# SCH_task-L2.net
KiCad netlist of a schematic drawn in EasyEDA
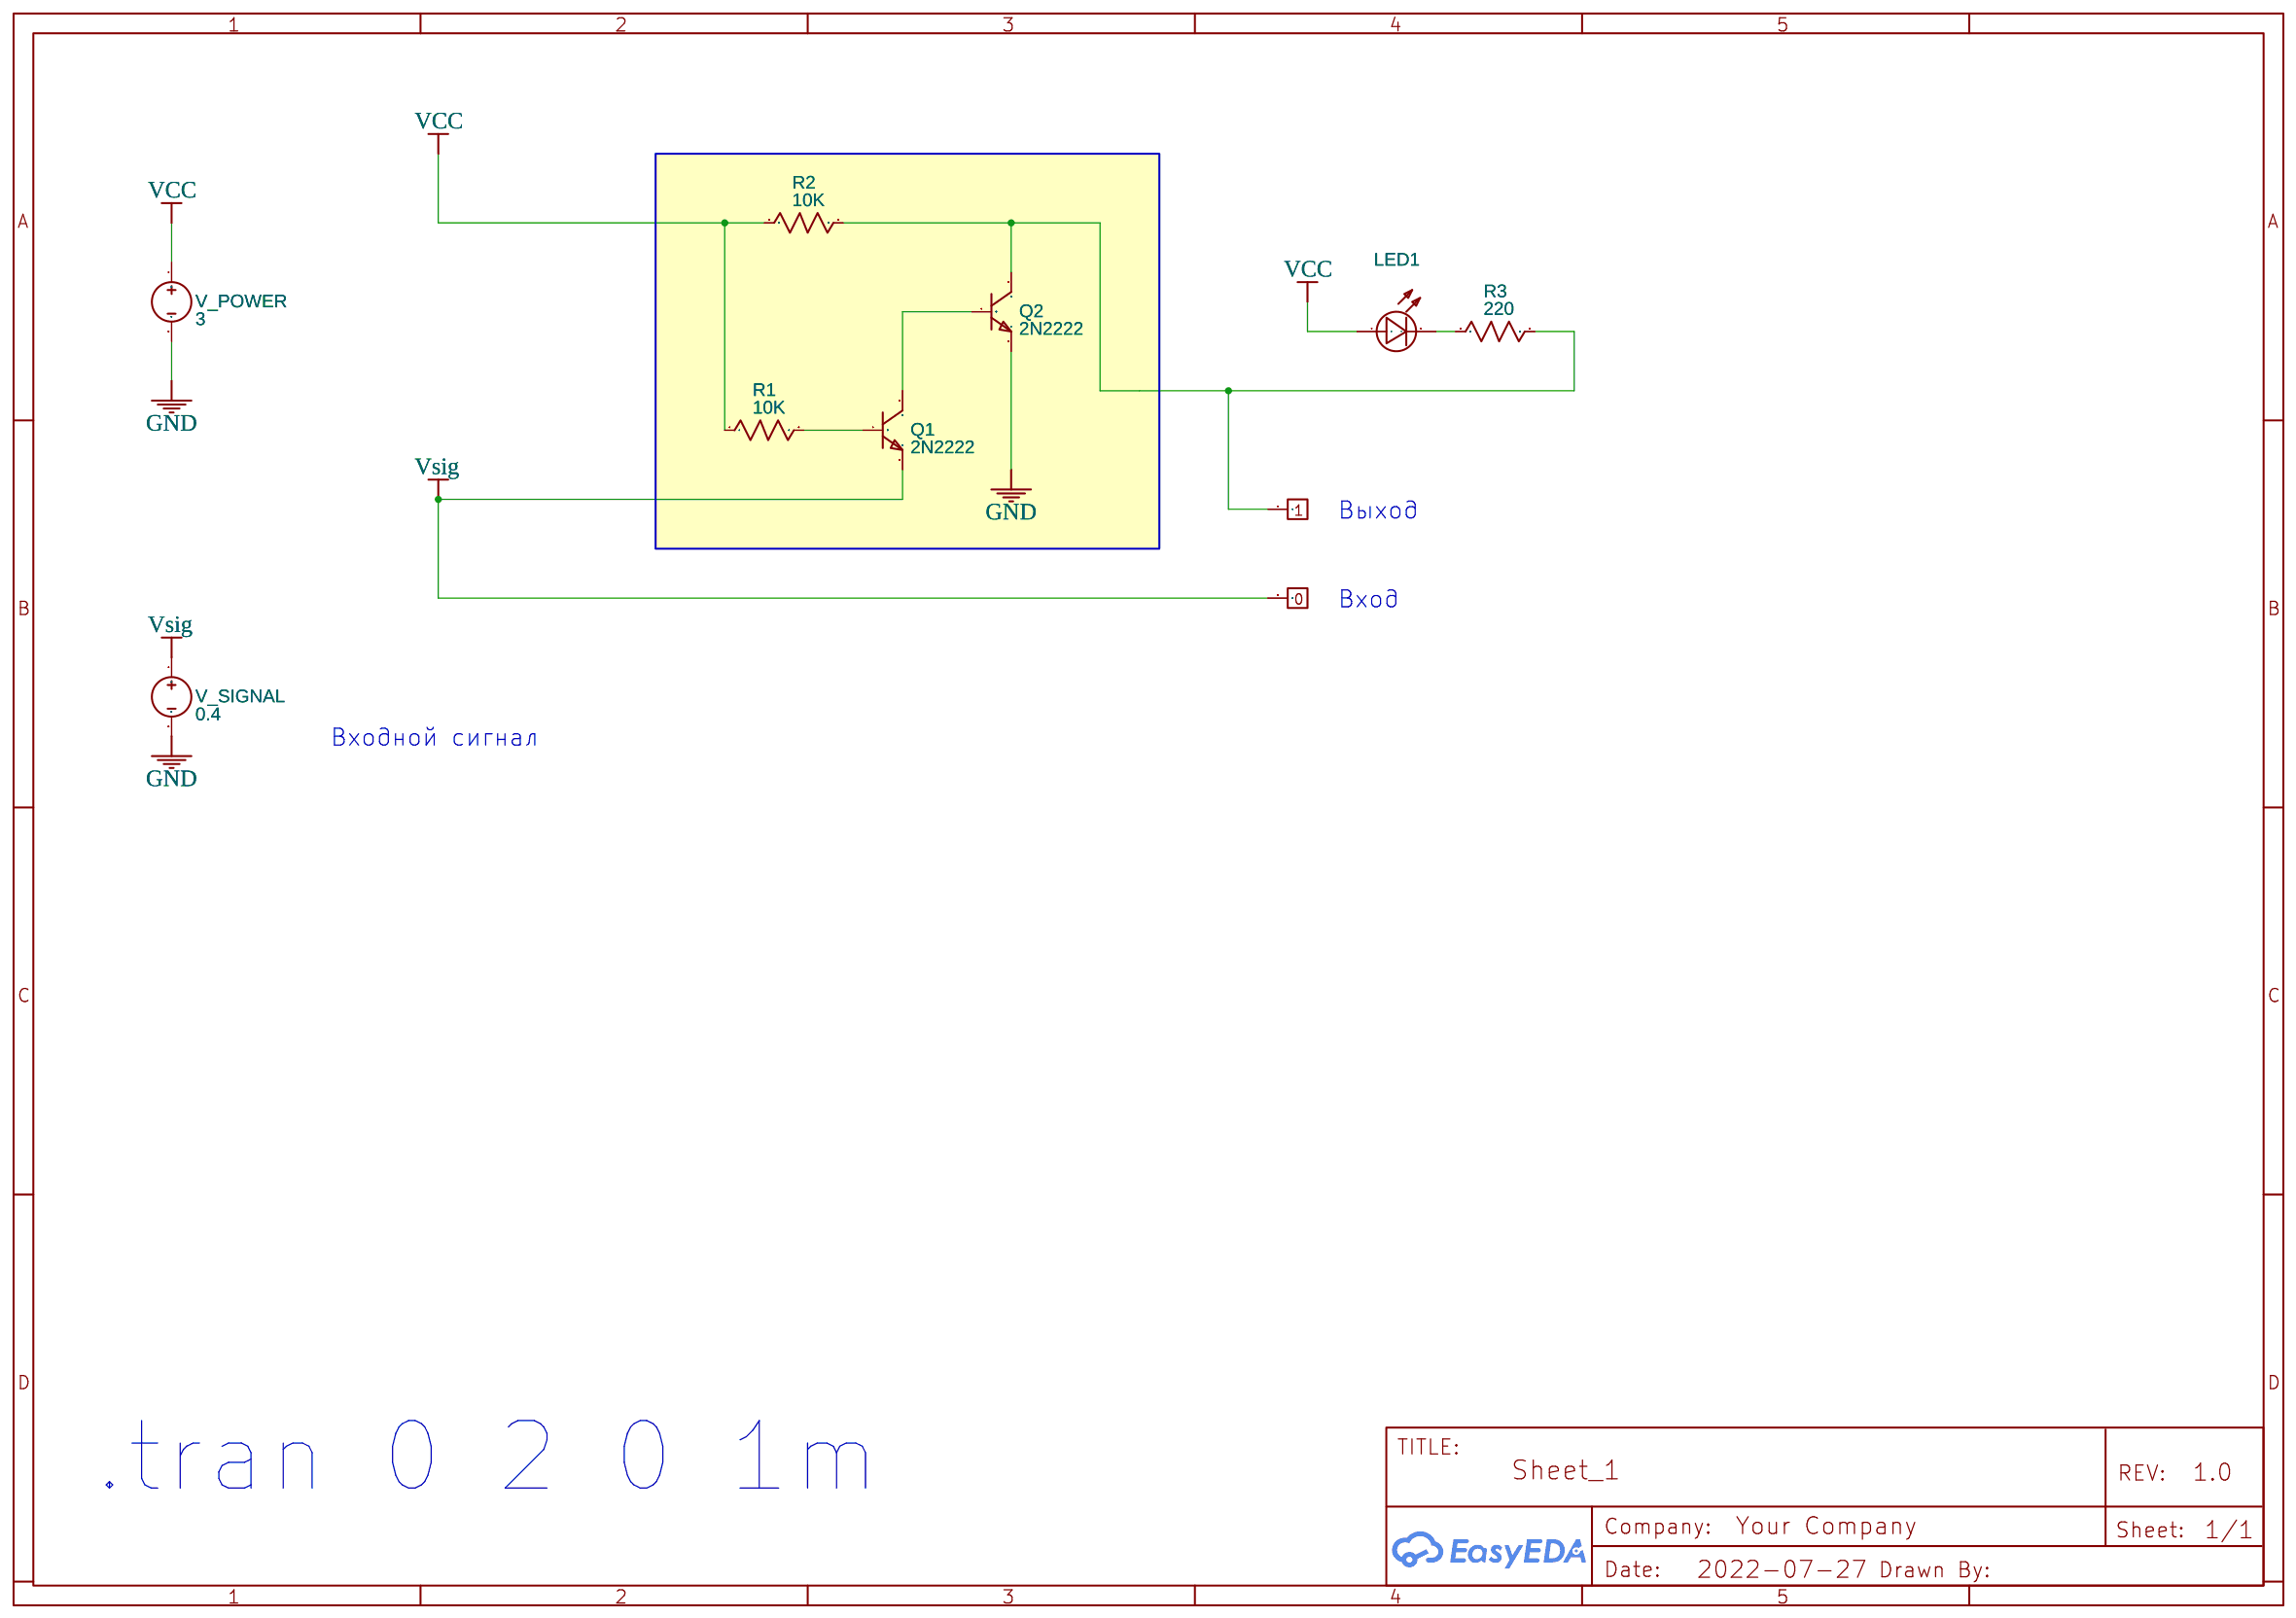
[diagram p0: schematic sheet]

(export (version "E")
  (design (tool "Eeschema 10.0.6"))
  (components
    (comp (ref "LED1") (value "LED") (libsource (lib "") (part "LED")))
    (comp (ref "Q1") (value "2N2222") (libsource (lib "") (part "2N2222")))
    (comp (ref "Q2") (value "2N2222") (libsource (lib "") (part "2N2222")))
    (comp (ref "R1") (value "10K") (libsource (lib "") (part "Resistor_US")))
    (comp (ref "R2") (value "10K") (libsource (lib "") (part "Resistor_US")))
    (comp (ref "R3") (value "220") (libsource (lib "") (part "Resistor_US")))
    (comp (ref "U1") (value "Logic_Probe") (libsource (lib "") (part "LOGICPROBE_1")))
    (comp (ref "U3") (value "Logic_Probe") (libsource (lib "") (part "LOGICPROBE")))
    (comp (ref "V_POWER") (value "3") (libsource (lib "") (part "VDC_1")))
    (comp (ref "V_SIGNAL") (value "0.4") (libsource (lib "") (part "VDC")))
  )
  (nets
    (net (code "1") (name "GND") (class "Default")
      (node (ref "Q2") (pin "2") (pinfunction "E_2") (pintype "unspecified"))
      (node (ref "V_POWER") (pin "2") (pinfunction "2_2") (pintype "unspecified"))
      (node (ref "V_SIGNAL") (pin "2") (pinfunction "2_2") (pintype "unspecified"))
    )
    (net (code "2") (name "Net-(LED1--)") (class "Default")
      (node (ref "LED1") (pin "2") (pinfunction "-_2") (pintype "unspecified"))
      (node (ref "R3") (pin "1") (pinfunction "1_1") (pintype "unspecified"))
    )
    (net (code "3") (name "Net-(Q1-B)") (class "Default")
      (node (ref "Q1") (pin "1") (pinfunction "B_1") (pintype "unspecified"))
      (node (ref "R1") (pin "2") (pinfunction "2_2") (pintype "unspecified"))
    )
    (net (code "4") (name "Net-(Q1-C)") (class "Default")
      (node (ref "Q1") (pin "3") (pinfunction "C_3") (pintype "unspecified"))
      (node (ref "Q2") (pin "1") (pinfunction "B_1") (pintype "unspecified"))
    )
    (net (code "5") (name "Net-(Q2-C)") (class "Default")
      (node (ref "Q2") (pin "3") (pinfunction "C_3") (pintype "unspecified"))
      (node (ref "R2") (pin "2") (pinfunction "2_2") (pintype "unspecified"))
      (node (ref "R3") (pin "2") (pinfunction "2_2") (pintype "unspecified"))
      (node (ref "U1") (pin "1") (pinfunction "1_1") (pintype "unspecified"))
    )
    (net (code "6") (name "VCC") (class "Default")
      (node (ref "LED1") (pin "1") (pinfunction "+_1") (pintype "unspecified"))
      (node (ref "R1") (pin "1") (pinfunction "1_1") (pintype "unspecified"))
      (node (ref "R2") (pin "1") (pinfunction "1_1") (pintype "unspecified"))
      (node (ref "V_POWER") (pin "1") (pinfunction "1_1") (pintype "unspecified"))
    )
    (net (code "7") (name "Vsig") (class "Default")
      (node (ref "Q1") (pin "2") (pinfunction "E_2") (pintype "unspecified"))
      (node (ref "U3") (pin "1") (pinfunction "1_1") (pintype "unspecified"))
      (node (ref "V_SIGNAL") (pin "1") (pinfunction "1_1") (pintype "unspecified"))
    )
  )
)
